# riffle-CT-mcv-0_1_0.net
KiCad netlist of a schematic drawn in EAGLE
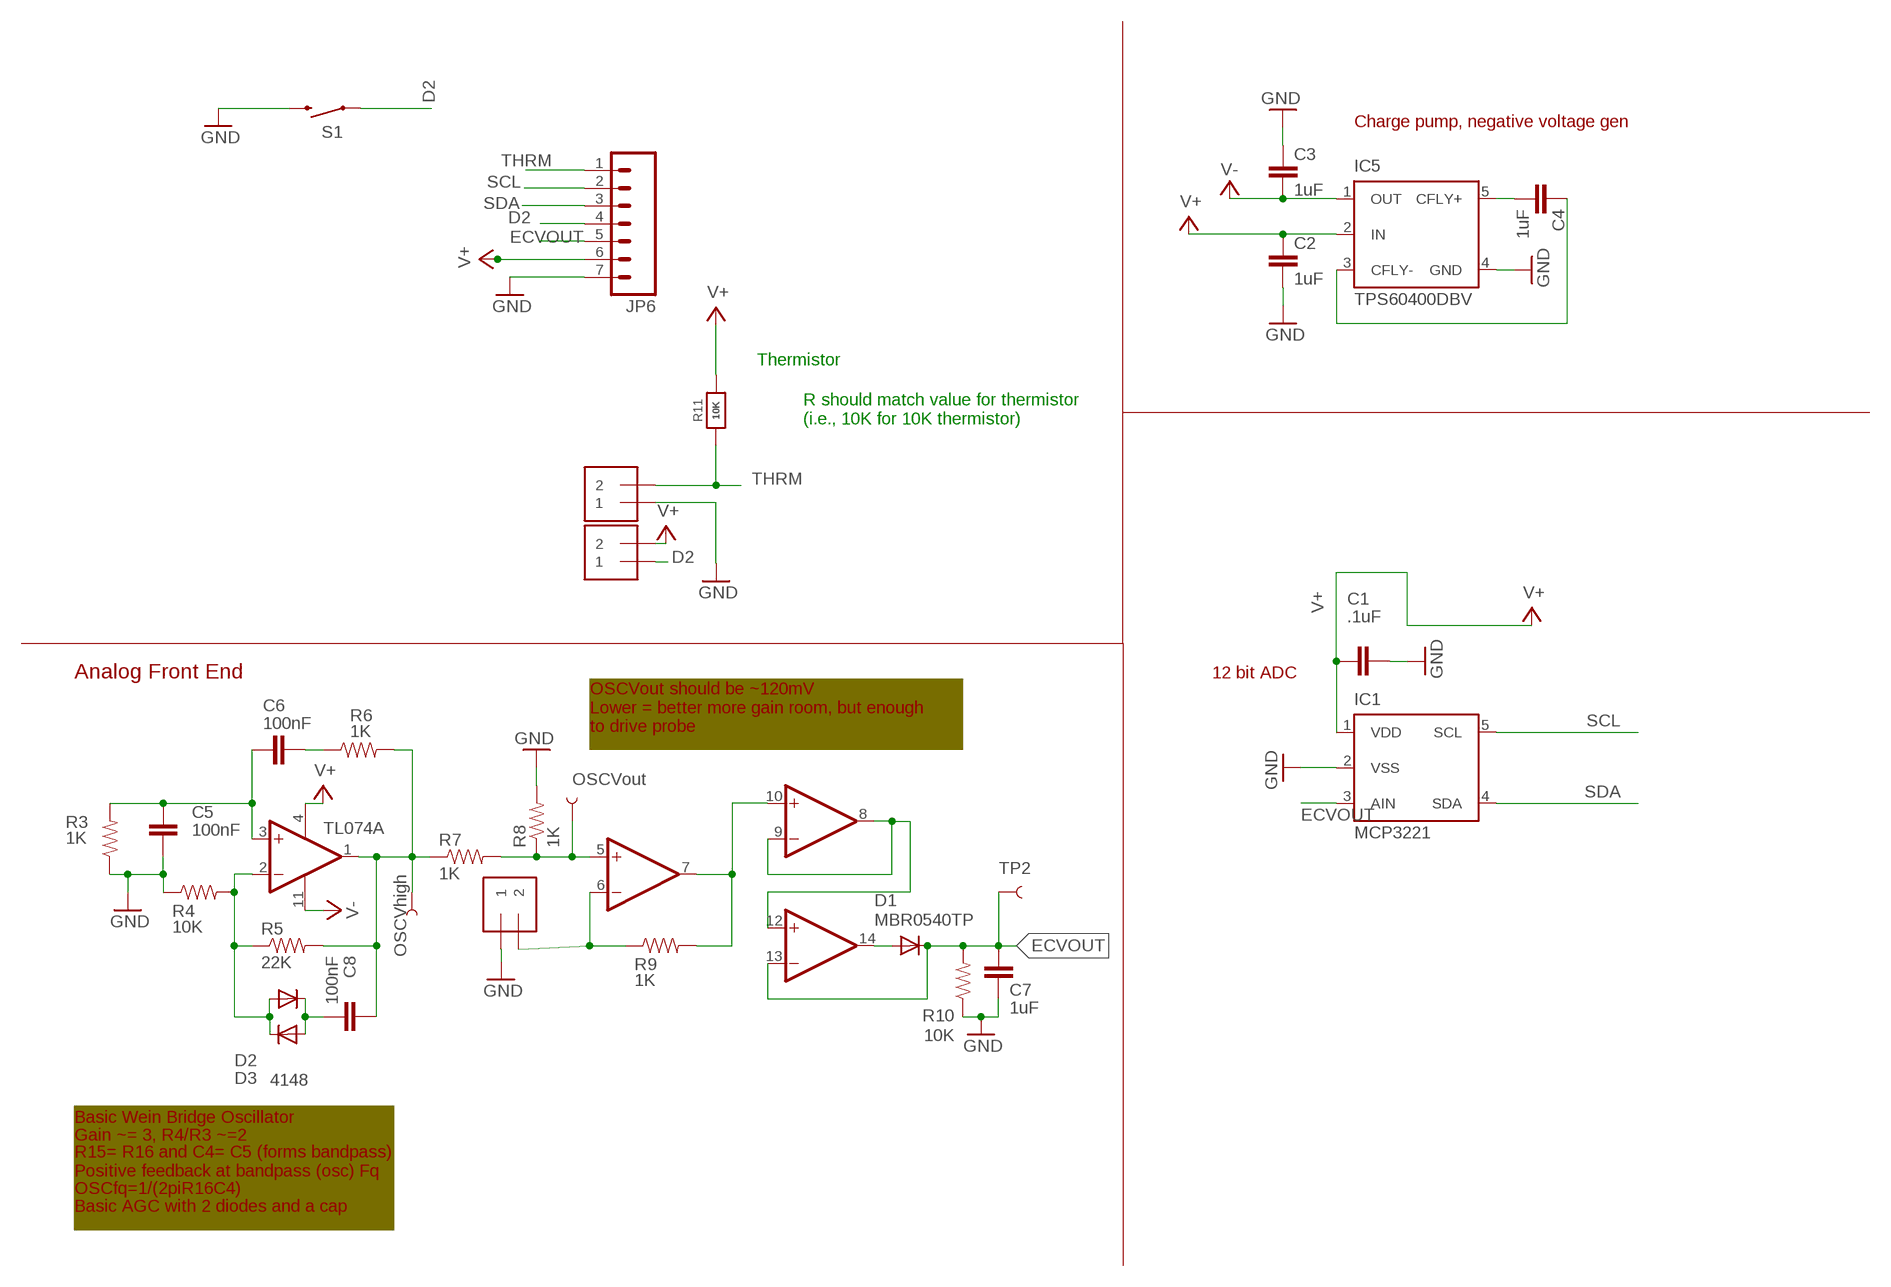
[diagram p0: schematic, sheet 1]

(export (version "E")
  (design (tool "Eeschema 10.0.6"))
  (components
    (comp (ref "1W")
      (value "1X2-3.5MM")
      (footprint "eagle-import:1X2-3.5MM")
      (libsource (lib "eagle-import") (part "1X2-3.5MM"))
    )
    (comp (ref "C1")
      (value ".1uF")
      (footprint "eagle-import:0805")
      (libsource (lib "eagle-import") (part "CAP0805"))
    )
    (comp (ref "C2")
      (value "1uF")
      (footprint "eagle-import:0805")
      (libsource (lib "eagle-import") (part "CAP0805"))
    )
    (comp (ref "C3")
      (value "1uF")
      (footprint "eagle-import:0805")
      (libsource (lib "eagle-import") (part "CAP0805"))
    )
    (comp (ref "C4")
      (value "1uF")
      (footprint "eagle-import:0805")
      (libsource (lib "eagle-import") (part "CAP0805"))
    )
    (comp (ref "C5")
      (value "100nF")
      (footprint "eagle-import:0805")
      (libsource (lib "eagle-import") (part "CAP0805"))
    )
    (comp (ref "C6")
      (value "100nF")
      (footprint "eagle-import:0805")
      (libsource (lib "eagle-import") (part "CAP0805"))
    )
    (comp (ref "C7")
      (value "1uF")
      (footprint "eagle-import:0805")
      (libsource (lib "eagle-import") (part "CAP0805"))
    )
    (comp (ref "C8")
      (value "100nF")
      (footprint "eagle-import:0805")
      (libsource (lib "eagle-import") (part "CAP0805"))
    )
    (comp (ref "D1")
      (value "MBR0540TP")
      (footprint "eagle-import:SOD123")
      (libsource (lib "eagle-import") (part "MBR0520LT"))
    )
    (comp (ref "D2")
      (value "4148")
      (footprint "eagle-import:SOD123")
      (libsource (lib "eagle-import") (part "MBR0520LT"))
    )
    (comp (ref "D3")
      (value "4148")
      (footprint "eagle-import:SOD123")
      (libsource (lib "eagle-import") (part "MBR0520LT"))
    )
    (comp (ref "EC")
      (value "1X2-3.5MM")
      (footprint "eagle-import:1X2-3.5MM")
      (libsource (lib "eagle-import") (part "1X2-3.5MM"))
    )
    (comp (ref "IC1")
      (value "MCP3221")
      (footprint "eagle-import:SOT23-DBV")
      (libsource (lib "eagle-import") (part "MCP3221"))
    )
    (comp (ref "IC5")
      (value "TPS60400DBV")
      (footprint "eagle-import:SOT23-DBV")
      (libsource (lib "eagle-import") (part "TPS60400DBV"))
    )
    (comp (ref "JP6")
      (value "M07")
      (footprint "eagle-import:1X07")
      (libsource (lib "eagle-import") (part "M07"))
    )
    (comp (ref "R3")
      (value "1K")
      (footprint "eagle-import:0805")
      (libsource (lib "eagle-import") (part "RESISTOR0805-RES"))
    )
    (comp (ref "R4")
      (value "10K")
      (footprint "eagle-import:0805")
      (libsource (lib "eagle-import") (part "RESISTOR0805-RES"))
    )
    (comp (ref "R5")
      (value "22K")
      (footprint "eagle-import:0805")
      (libsource (lib "eagle-import") (part "RESISTOR0805-RES"))
    )
    (comp (ref "R6")
      (value "1K")
      (footprint "eagle-import:0805")
      (libsource (lib "eagle-import") (part "RESISTOR0805-RES"))
    )
    (comp (ref "R7")
      (value "1K")
      (footprint "eagle-import:0805")
      (libsource (lib "eagle-import") (part "RESISTOR0805-RES"))
    )
    (comp (ref "R8")
      (value "1K")
      (footprint "eagle-import:0805")
      (libsource (lib "eagle-import") (part "RESISTOR0805-RES"))
    )
    (comp (ref "R9")
      (value "1K")
      (footprint "eagle-import:0805")
      (libsource (lib "eagle-import") (part "RESISTOR0805-RES"))
    )
    (comp (ref "R10")
      (value "10K")
      (footprint "eagle-import:0805")
      (libsource (lib "eagle-import") (part "RESISTOR0805-RES"))
    )
    (comp (ref "R11")
      (value "10K")
      (footprint "eagle-import:0603-NO")
      (libsource (lib "eagle-import") (part "RESISTOR_0603_NOOUT"))
    )
    (comp (ref "S1")
      (value "REED")
      (footprint "eagle-import:REED_SWITCH_PLASTIC")
      (libsource (lib "eagle-import") (part "SWITCH-MOMENTARY-2PTH_REED2"))
    )
    (comp (ref "THRM")
      (value "1X2-3.5MM")
      (footprint "eagle-import:1X2-3.5MM")
      (libsource (lib "eagle-import") (part "1X2-3.5MM"))
    )
    (comp (ref "TL074")
      (value "TL074")
      (footprint "eagle-import:SO14")
      (libsource (lib "eagle-import") (part "QUADOPAMPM"))
    )
    (comp (ref "TP2")
      (value "TEST-POINT3")
      (footprint "eagle-import:PAD.03X.03")
      (libsource (lib "eagle-import") (part "TEST-POINT3"))
    )
    (comp (ref "TP3")
      (value "OSCVhigh")
      (footprint "eagle-import:PAD.03X.03")
      (libsource (lib "eagle-import") (part "TEST-POINT3"))
    )
    (comp (ref "TP5")
      (value "OSCVout")
      (footprint "eagle-import:PAD.03X.03")
      (libsource (lib "eagle-import") (part "TEST-POINT3"))
    )
  )
  (nets
    (net (code "1") (name "/D2") (class "Default")
      (node (ref "1W") (pin "1") (pinfunction "1_1") (pintype "passive"))
      (node (ref "JP6") (pin "4") (pinfunction "4_4") (pintype "passive"))
      (node (ref "S1") (pin "P$1") (pinfunction "1_P$1") (pintype "passive"))
    )
    (net (code "2") (name "/SCL") (class "Default")
      (node (ref "IC1") (pin "5") (pinfunction "SCL_5") (pintype "bidirectional"))
      (node (ref "JP6") (pin "2") (pinfunction "2_2") (pintype "passive"))
    )
    (net (code "3") (name "/SDA") (class "Default")
      (node (ref "IC1") (pin "4") (pinfunction "SDA_4") (pintype "bidirectional"))
      (node (ref "JP6") (pin "3") (pinfunction "3_3") (pintype "passive"))
    )
    (net (code "4") (name "/THRM") (class "Default")
      (node (ref "JP6") (pin "1") (pinfunction "1_1") (pintype "passive"))
      (node (ref "R11") (pin "1") (pinfunction "1_1") (pintype "passive"))
      (node (ref "THRM") (pin "2") (pinfunction "2_2") (pintype "passive"))
    )
    (net (code "5") (name "ECVOUT") (class "Default")
      (node (ref "C7") (pin "2") (pinfunction "2_2") (pintype "passive"))
      (node (ref "D1") (pin "C") (pinfunction "C_C") (pintype "passive"))
      (node (ref "IC1") (pin "3") (pinfunction "AIN_3") (pintype "input"))
      (node (ref "JP6") (pin "5") (pinfunction "5_5") (pintype "passive"))
      (node (ref "R10") (pin "2") (pinfunction "2_2") (pintype "passive"))
      (node (ref "TL074") (pin "13") (pinfunction "-IN_13") (pintype "input"))
      (node (ref "TP2") (pin "P$1") (pinfunction "1_P$1") (pintype "bidirectional"))
    )
    (net (code "6") (name "GND") (class "Default")
      (node (ref "C1") (pin "1") (pinfunction "1_1") (pintype "passive"))
      (node (ref "C2") (pin "2") (pinfunction "2_2") (pintype "passive"))
      (node (ref "C3") (pin "1") (pinfunction "1_1") (pintype "passive"))
      (node (ref "C5") (pin "1") (pinfunction "1_1") (pintype "passive"))
      (node (ref "C7") (pin "1") (pinfunction "1_1") (pintype "passive"))
      (node (ref "EC") (pin "1") (pinfunction "1_1") (pintype "passive"))
      (node (ref "IC1") (pin "2") (pinfunction "VSS_2") (pintype "power_in"))
      (node (ref "IC5") (pin "4") (pinfunction "GND_4") (pintype "passive"))
      (node (ref "JP6") (pin "7") (pinfunction "7_7") (pintype "passive"))
      (node (ref "R10") (pin "1") (pinfunction "1_1") (pintype "passive"))
      (node (ref "R3") (pin "1") (pinfunction "1_1") (pintype "passive"))
      (node (ref "R4") (pin "1") (pinfunction "1_1") (pintype "passive"))
      (node (ref "R8") (pin "2") (pinfunction "2_2") (pintype "passive"))
      (node (ref "S1") (pin "P$2") (pinfunction "2_P$2") (pintype "passive"))
      (node (ref "THRM") (pin "1") (pinfunction "1_1") (pintype "passive"))
    )
    (net (code "7") (name "Net-(C6-Pad1)") (class "Default")
      (node (ref "C6") (pin "1") (pinfunction "1_1") (pintype "passive"))
      (node (ref "R6") (pin "1") (pinfunction "1_1") (pintype "passive"))
    )
    (net (code "8") (name "Net-(C8-Pad2)") (class "Default")
      (node (ref "C8") (pin "2") (pinfunction "2_2") (pintype "passive"))
      (node (ref "D2") (pin "C") (pinfunction "C_C") (pintype "passive"))
      (node (ref "D3") (pin "A") (pinfunction "A_A") (pintype "passive"))
    )
    (net (code "9") (name "Net-(IC5-CFLY+)") (class "Default")
      (node (ref "C4") (pin "2") (pinfunction "2_2") (pintype "passive"))
      (node (ref "IC5") (pin "5") (pinfunction "CFLY+_5") (pintype "passive"))
    )
    (net (code "10") (name "Net-(IC5-CFLY-)") (class "Default")
      (node (ref "C4") (pin "1") (pinfunction "1_1") (pintype "passive"))
      (node (ref "IC5") (pin "3") (pinfunction "CFLY-_3") (pintype "power_in"))
    )
    (net (code "11") (name "Net-(TL074A-+IN)") (class "Default")
      (node (ref "C5") (pin "2") (pinfunction "2_2") (pintype "passive"))
      (node (ref "C6") (pin "2") (pinfunction "2_2") (pintype "passive"))
      (node (ref "R3") (pin "2") (pinfunction "2_2") (pintype "passive"))
      (node (ref "TL074") (pin "3") (pinfunction "+IN_3") (pintype "input"))
    )
    (net (code "12") (name "Net-(TL074A--IN)") (class "Default")
      (node (ref "D2") (pin "A") (pinfunction "A_A") (pintype "passive"))
      (node (ref "D3") (pin "C") (pinfunction "C_C") (pintype "passive"))
      (node (ref "R4") (pin "2") (pinfunction "2_2") (pintype "passive"))
      (node (ref "R5") (pin "1") (pinfunction "1_1") (pintype "passive"))
      (node (ref "TL074") (pin "2") (pinfunction "-IN_2") (pintype "input"))
    )
    (net (code "13") (name "Net-(TL074A-OUT)") (class "Default")
      (node (ref "C8") (pin "1") (pinfunction "1_1") (pintype "passive"))
      (node (ref "R5") (pin "2") (pinfunction "2_2") (pintype "passive"))
      (node (ref "R6") (pin "2") (pinfunction "2_2") (pintype "passive"))
      (node (ref "R7") (pin "1") (pinfunction "1_1") (pintype "passive"))
      (node (ref "TL074") (pin "1") (pinfunction "OUT_1") (pintype "output"))
      (node (ref "TP3") (pin "P$1") (pinfunction "1_P$1") (pintype "bidirectional"))
    )
    (net (code "14") (name "Net-(TL074B-+IN)") (class "Default")
      (node (ref "R7") (pin "2") (pinfunction "2_2") (pintype "passive"))
      (node (ref "R8") (pin "1") (pinfunction "1_1") (pintype "passive"))
      (node (ref "TL074") (pin "5") (pinfunction "+IN_5") (pintype "input"))
      (node (ref "TP5") (pin "P$1") (pinfunction "1_P$1") (pintype "bidirectional"))
    )
    (net (code "15") (name "Net-(TL074B--IN)") (class "Default")
      (node (ref "EC") (pin "2") (pinfunction "2_2") (pintype "passive"))
      (node (ref "R9") (pin "1") (pinfunction "1_1") (pintype "passive"))
      (node (ref "TL074") (pin "6") (pinfunction "-IN_6") (pintype "input"))
    )
    (net (code "16") (name "Net-(TL074B-OUT)") (class "Default")
      (node (ref "R9") (pin "2") (pinfunction "2_2") (pintype "passive"))
      (node (ref "TL074") (pin "10") (pinfunction "+IN_10") (pintype "input"))
      (node (ref "TL074") (pin "7") (pinfunction "OUT_7") (pintype "output"))
    )
    (net (code "17") (name "Net-(TL074C--IN)") (class "Default")
      (node (ref "TL074") (pin "12") (pinfunction "+IN_12") (pintype "input"))
      (node (ref "TL074") (pin "8") (pinfunction "OUT_8") (pintype "output"))
      (node (ref "TL074") (pin "9") (pinfunction "-IN_9") (pintype "input"))
    )
    (net (code "18") (name "Net-(TL074D-OUT)") (class "Default")
      (node (ref "D1") (pin "A") (pinfunction "A_A") (pintype "passive"))
      (node (ref "TL074") (pin "14") (pinfunction "OUT_14") (pintype "output"))
    )
    (net (code "19") (name "V+") (class "Default")
      (node (ref "1W") (pin "2") (pinfunction "2_2") (pintype "passive"))
      (node (ref "C1") (pin "2") (pinfunction "2_2") (pintype "passive"))
      (node (ref "C2") (pin "1") (pinfunction "1_1") (pintype "passive"))
      (node (ref "IC1") (pin "1") (pinfunction "VDD_1") (pintype "power_in"))
      (node (ref "IC5") (pin "2") (pinfunction "IN_2") (pintype "input"))
      (node (ref "JP6") (pin "6") (pinfunction "6_6") (pintype "passive"))
      (node (ref "R11") (pin "2") (pinfunction "2_2") (pintype "passive"))
      (node (ref "TL074") (pin "4") (pinfunction "V+_4") (pintype "power_in"))
    )
    (net (code "20") (name "V-") (class "Default")
      (node (ref "C3") (pin "2") (pinfunction "2_2") (pintype "passive"))
      (node (ref "IC5") (pin "1") (pinfunction "OUT_1") (pintype "input"))
      (node (ref "TL074") (pin "11") (pinfunction "V-_11") (pintype "power_in"))
    )
  )
)
